# FE_Channel.net
KiCad netlist of a schematic drawn in Altium Designer
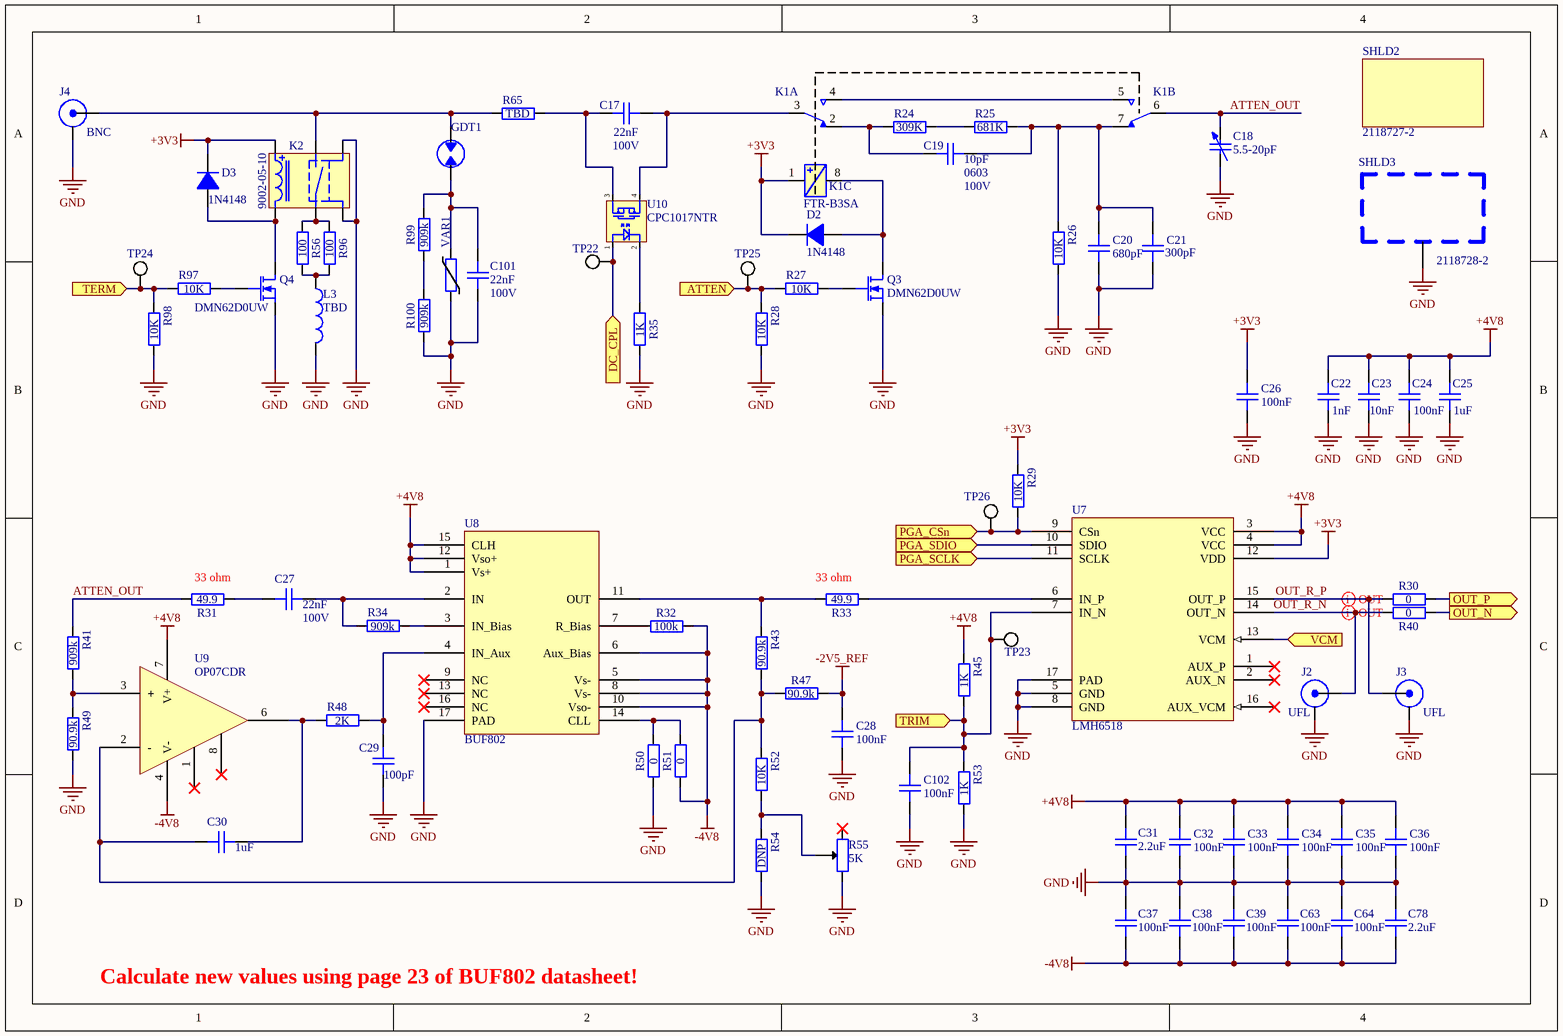
[diagram p0: FE_Channel.SchDoc]

(export (version "E")
  (design (tool "Eeschema 10.0.6"))
  (components
    (comp (ref "C17")
      (value "22nF")
      (footprint "GEN_C_0603")
      (fields (field (name "VOLTAGE RATING") "100V"))
      (libsource (lib "DSO") (part "CAP 22nF 100V X7R 0603"))
    )
    (comp (ref "C18")
      (value "5.5-20pF")
      (footprint "EW_TRIMCAP")
      (libsource (lib "DSO") (part "CAP TRIMMER 5.5-20PF 500V"))
    )
    (comp (ref "C19")
      (value "10pF")
      (footprint "GEN_C_0603")
      (fields (field (name "PACKAGE") "0603") (field (name "VOLTAGE RATING") "100V"))
      (libsource (lib "DSO") (part "CAP 10pF 100V C0G 0603"))
    )
    (comp (ref "C20")
      (value "680pF")
      (footprint "GEN_C_0402")
      (libsource (lib "DSO") (part "CAP 680pF 50V C0G 0402"))
    )
    (comp (ref "C21")
      (value "300pF")
      (footprint "GEN_C_0402")
      (libsource (lib "DSO") (part "CAP 300pF 50V C0G 0402"))
    )
    (comp (ref "C22")
      (value "1nF")
      (footprint "GEN_C_0402")
      (libsource (lib "DSO") (part "CAP 1nF 50V C0G 0402"))
    )
    (comp (ref "C23")
      (value "10nF")
      (footprint "GEN_C_0402")
      (libsource (lib "DSO") (part "CAP 10nF 50V X7R 0402"))
    )
    (comp (ref "C24")
      (value "100nF")
      (footprint "GEN_C_0402")
      (libsource (lib "DSO") (part "CAP 100nF 16V X7R 0402"))
    )
    (comp (ref "C25")
      (value "1uF")
      (footprint "GEN_C_0402")
      (libsource (lib "DSO") (part "CAP 1uF 25V X5R 0402"))
    )
    (comp (ref "C26")
      (value "100nF")
      (footprint "GEN_C_0402")
      (libsource (lib "DSO") (part "CAP 100nF 16V X7R 0402"))
    )
    (comp (ref "C27")
      (value "22nF")
      (footprint "GEN_C_0603")
      (fields (field (name "VOLTAGE RATING") "100V"))
      (libsource (lib "DSO") (part "CAP 22nF 100V X7R 0603"))
    )
    (comp (ref "C28")
      (value "100nF")
      (footprint "GEN_C_0402")
      (libsource (lib "DSO") (part "CAP 100nF 16V X7R 0402"))
    )
    (comp (ref "C29")
      (value "100pF")
      (footprint "GEN_C_0402")
      (libsource (lib "DSO") (part "CAP 100pF 50V C0G 0402"))
    )
    (comp (ref "C30")
      (value "1uF")
      (footprint "GEN_C_0402")
      (libsource (lib "DSO") (part "CAP 1uF 25V X5R 0402"))
    )
    (comp (ref "C31")
      (value "2.2uF")
      (footprint "GEN_C_0402")
      (libsource (lib "DSO") (part "CAP 2.2uF 10V X5R 0402"))
    )
    (comp (ref "C32")
      (value "100nF")
      (footprint "GEN_C_0402")
      (libsource (lib "DSO") (part "CAP 100nF 16V X7R 0402"))
    )
    (comp (ref "C33")
      (value "100nF")
      (footprint "GEN_C_0402")
      (libsource (lib "DSO") (part "CAP 100nF 16V X7R 0402"))
    )
    (comp (ref "C34")
      (value "100nF")
      (footprint "GEN_C_0402")
      (libsource (lib "DSO") (part "CAP 100nF 16V X7R 0402"))
    )
    (comp (ref "C35")
      (value "100nF")
      (footprint "GEN_C_0402")
      (libsource (lib "DSO") (part "CAP 100nF 16V X7R 0402"))
    )
    (comp (ref "C36")
      (value "100nF")
      (footprint "GEN_C_0402")
      (libsource (lib "DSO") (part "CAP 100nF 16V X7R 0402"))
    )
    (comp (ref "C37")
      (value "100nF")
      (footprint "GEN_C_0402")
      (libsource (lib "DSO") (part "CAP 100nF 16V X7R 0402"))
    )
    (comp (ref "C38")
      (value "100nF")
      (footprint "GEN_C_0402")
      (libsource (lib "DSO") (part "CAP 100nF 16V X7R 0402"))
    )
    (comp (ref "C39")
      (value "100nF")
      (footprint "GEN_C_0402")
      (libsource (lib "DSO") (part "CAP 100nF 16V X7R 0402"))
    )
    (comp (ref "C63")
      (value "100nF")
      (footprint "GEN_C_0402")
      (libsource (lib "DSO") (part "CAP 100nF 16V X7R 0402"))
    )
    (comp (ref "C64")
      (value "100nF")
      (footprint "GEN_C_0402")
      (libsource (lib "DSO") (part "CAP 100nF 16V X7R 0402"))
    )
    (comp (ref "C78")
      (value "2.2uF")
      (footprint "GEN_C_0402")
      (libsource (lib "DSO") (part "CAP 2.2uF 10V X5R 0402"))
    )
    (comp (ref "C101")
      (value "22nF")
      (footprint "GEN_C_0603")
      (fields (field (name "VOLTAGE RATING") "100V"))
      (libsource (lib "DSO") (part "CAP 22nF 100V X7R 0603"))
    )
    (comp (ref "C102")
      (value "100nF")
      (footprint "GEN_C_0402")
      (libsource (lib "DSO") (part "CAP 100nF 16V X7R 0402"))
    )
    (comp (ref "D2") (value "1N4148") (footprint "GEN_SOD_323") (libsource (lib "DSO") (part "DIODE 1N4148")))
    (comp (ref "D3") (value "1N4148") (footprint "GEN_SOD_323") (libsource (lib "DSO") (part "DIODE 1N4148")))
    (comp (ref "GDT1")
      (value "4532-075-LF")
      (footprint "BOU_2051")
      (libsource (lib "DSO") (part "GDT 75V 1812"))
    )
    (comp (ref "J2") (value "UFL") (footprint "TE_2334884-1") (libsource (lib "DSO") (part "UFL Jack SMD")))
    (comp (ref "J3") (value "UFL") (footprint "TE_2334884-1") (libsource (lib "DSO") (part "UFL Jack SMD")))
    (comp (ref "J4") (value "BNC") (footprint "MOL_0731000105") (libsource (lib "DSO") (part "BNC JACK R/A")))
    (comp (ref "K1")
      (value "FTR-B3SA")
      (footprint "FUJ_FTR-B3SA")
      (libsource (lib "DSO") (part "RELAY DPDT-NO FTR-B3SA"))
    )
    (comp (ref "K2")
      (value "9002-05-10")
      (footprint "COTO_9002-05-10")
      (libsource (lib "DSO") (part "RELAY RF SPST-NO 9002-05-10"))
    )
    (comp (ref "L3") (value "TBD") (footprint "GEN_L_0402") (libsource (lib "DSO") (part "IND TBD 0402")))
    (comp (ref "Q3")
      (value "DMN62D0UW")
      (footprint "GEN_SOT_323")
      (libsource (lib "DSO") (part "NMOS DMN62D0UW"))
    )
    (comp (ref "Q4")
      (value "DMN62D0UW")
      (footprint "GEN_SOT_323")
      (libsource (lib "DSO") (part "NMOS DMN62D0UW"))
    )
    (comp (ref "R24")
      (value "309K")
      (footprint "GEN_R_0402")
      (fields (field (name "TOLERANCE") "1%"))
      (libsource (lib "DSO") (part "RES 309K OHM 1% 1/16W 0402"))
    )
    (comp (ref "R25")
      (value "681K")
      (footprint "GEN_R_0402")
      (fields (field (name "TOLERANCE") "1%"))
      (libsource (lib "DSO") (part "RES 681K OHM 1% 1/16W 0402"))
    )
    (comp (ref "R26")
      (value "10K")
      (footprint "GEN_R_0402")
      (fields (field (name "TOLERANCE") "1%"))
      (libsource (lib "DSO") (part "RES 10K OHM 1% 1/10W 0402"))
    )
    (comp (ref "R27")
      (value "10K")
      (footprint "GEN_R_0402")
      (fields (field (name "TOLERANCE") "1%"))
      (libsource (lib "") (part "RES 10K OHM 1% 1/10W 0402_1"))
    )
    (comp (ref "R28")
      (value "10K")
      (footprint "GEN_R_0402")
      (fields (field (name "TOLERANCE") "1%"))
      (libsource (lib "DSO") (part "RES 10K OHM 1% 1/10W 0402"))
    )
    (comp (ref "R29")
      (value "10K")
      (footprint "GEN_R_0402")
      (fields (field (name "TOLERANCE") "1%"))
      (libsource (lib "DSO") (part "RES 10K OHM 1% 1/10W 0402"))
    )
    (comp (ref "R30")
      (value "0")
      (footprint "GEN_R_0402")
      (libsource (lib "") (part "RES 0 OHM 1/16W 0402_1"))
    )
    (comp (ref "R31")
      (value "49.9")
      (footprint "GEN_R_0402")
      (fields (field (name "TOLERANCE") "1%"))
      (libsource (lib "DSO") (part "RES 49.9 OHM 1% 1/10W 0402"))
    )
    (comp (ref "R32")
      (value "100k")
      (footprint "GEN_R_0402")
      (fields (field (name "TOLERANCE") "1%"))
      (libsource (lib "DSO") (part "RES 100K OHM 1% 1/10W 0402"))
    )
    (comp (ref "R33")
      (value "49.9")
      (footprint "GEN_R_0402")
      (fields (field (name "TOLERANCE") "1%"))
      (libsource (lib "DSO") (part "RES 49.9 OHM 1% 1/10W 0402"))
    )
    (comp (ref "R34")
      (value "909k")
      (footprint "GEN_R_0402")
      (fields (field (name "TOLERANCE") "1%"))
      (libsource (lib "DSO") (part "RES 909K OHM 1% 1/16W 0402"))
    )
    (comp (ref "R35")
      (value "1K")
      (footprint "GEN_R_0402")
      (fields (field (name "TOLERANCE") "1%"))
      (libsource (lib "") (part "RES 1K OHM 1% 1/10W 0402_1"))
    )
    (comp (ref "R40")
      (value "0")
      (footprint "GEN_R_0402")
      (libsource (lib "") (part "RES 0 OHM 1/16W 0402_1"))
    )
    (comp (ref "R41")
      (value "909k")
      (footprint "GEN_R_0402")
      (fields (field (name "TOLERANCE") "1%"))
      (libsource (lib "") (part "RES 909K OHM 1% 1/16W 0402_1"))
    )
    (comp (ref "R43")
      (value "90.9k")
      (footprint "GEN_R_0402")
      (fields (field (name "TOLERANCE") "1%"))
      (libsource (lib "DSO") (part "RES 90.9K OHM 1% 1/16W 0402"))
    )
    (comp (ref "R45")
      (value "1K")
      (footprint "GEN_R_0402")
      (fields (field (name "TOLERANCE") "1%"))
      (libsource (lib "DSO") (part "RES 1K OHM 1% 1/10W 0402"))
    )
    (comp (ref "R47")
      (value "90.9k")
      (footprint "GEN_R_0402")
      (fields (field (name "TOLERANCE") "1%"))
      (libsource (lib "") (part "RES 90.9K OHM 1% 1/16W 0402_1"))
    )
    (comp (ref "R48")
      (value "2K")
      (footprint "GEN_R_0402")
      (fields (field (name "TOLERANCE") "1%"))
      (libsource (lib "DSO") (part "RES 2K OHM 1% 1/16W 0402"))
    )
    (comp (ref "R49")
      (value "90.9k")
      (footprint "GEN_R_0402")
      (fields (field (name "TOLERANCE") "1%"))
      (libsource (lib "DSO") (part "RES 90.9K OHM 1% 1/16W 0402"))
    )
    (comp (ref "R50")
      (value "0")
      (footprint "GEN_R_0402")
      (libsource (lib "DSO") (part "RES 0 OHM 1/16W 0402"))
    )
    (comp (ref "R51")
      (value "0")
      (footprint "GEN_R_0402")
      (libsource (lib "DSO") (part "RES 0 OHM 1/16W 0402"))
    )
    (comp (ref "R52")
      (value "10K")
      (footprint "GEN_R_0402")
      (fields (field (name "TOLERANCE") "1%"))
      (libsource (lib "DSO") (part "RES 10K OHM 1% 1/10W 0402"))
    )
    (comp (ref "R53")
      (value "1K")
      (footprint "GEN_R_0402")
      (fields (field (name "TOLERANCE") "1%"))
      (libsource (lib "DSO") (part "RES 1K OHM 1% 1/10W 0402"))
    )
    (comp (ref "R54")
      (value "DNP")
      (footprint "GEN_R_0402")
      (fields (field (name "TOLERANCE") "1%"))
      (libsource (lib "DSO") (part "RES DNP 0402"))
    )
    (comp (ref "R55")
      (value "5K")
      (footprint "BOU_3mm_POT")
      (fields (field (name "TOLERANCE") "1%"))
      (libsource (lib "DSO") (part "TRIMMER 5K OHM 0.1W J LEAD TOP"))
    )
    (comp (ref "R56")
      (value "100")
      (footprint "GEN_R_0402")
      (fields (field (name "TOLERANCE") "1%"))
      (libsource (lib "DSO") (part "RES 100 OHM 1% 1/10W 0402"))
    )
    (comp (ref "R65") (value "TBD") (footprint "GEN_R_0603") (libsource (lib "DSO") (part "RES TBD 0603")))
    (comp (ref "R96")
      (value "100")
      (footprint "GEN_R_0402")
      (fields (field (name "TOLERANCE") "1%"))
      (libsource (lib "DSO") (part "RES 100 OHM 1% 1/10W 0402"))
    )
    (comp (ref "R97")
      (value "10K")
      (footprint "GEN_R_0402")
      (fields (field (name "TOLERANCE") "1%"))
      (libsource (lib "") (part "RES 10K OHM 1% 1/10W 0402_1"))
    )
    (comp (ref "R98")
      (value "10K")
      (footprint "GEN_R_0402")
      (fields (field (name "TOLERANCE") "1%"))
      (libsource (lib "DSO") (part "RES 10K OHM 1% 1/10W 0402"))
    )
    (comp (ref "R99")
      (value "909k")
      (footprint "GEN_R_0402")
      (fields (field (name "TOLERANCE") "1%"))
      (libsource (lib "") (part "RES 909K OHM 1% 1/16W 0402_1"))
    )
    (comp (ref "R100")
      (value "909k")
      (footprint "GEN_R_0402")
      (fields (field (name "TOLERANCE") "1%"))
      (libsource (lib "") (part "RES 909K OHM 1% 1/16W 0402_1"))
    )
    (comp (ref "SHLD2") (value "2118727-2") (libsource (lib "DSO") (part "SHIELD 2118727-2")))
    (comp (ref "SHLD3")
      (value "2118728-2")
      (footprint "TE_2118728-2")
      (libsource (lib "DSO") (part "SHIELD 2118728-2"))
    )
    (comp (ref "TP22") (value "PCB") (footprint "GEN_TP_PCB") (libsource (lib "DSO") (part "TP PCB 1mm")))
    (comp (ref "TP23") (value "PCB") (footprint "GEN_TP_PCB") (libsource (lib "DSO") (part "TP PCB 1mm")))
    (comp (ref "TP24") (value "PCB") (footprint "GEN_TP_PCB") (libsource (lib "DSO") (part "TP PCB 1mm")))
    (comp (ref "TP25") (value "PCB") (footprint "GEN_TP_PCB") (libsource (lib "DSO") (part "TP PCB 1mm")))
    (comp (ref "TP26") (value "PCB") (footprint "GEN_TP_PCB") (libsource (lib "DSO") (part "TP PCB 1mm")))
    (comp (ref "U7")
      (value "LMH6518")
      (footprint "TI_WQFN_RGH0016A")
      (libsource (lib "DSO") (part "IC PGA LMH6518"))
    )
    (comp (ref "U8")
      (value "BUF802")
      (footprint "TI_VQFN_RGT0016C")
      (libsource (lib "DSO") (part "IC BUFFER AMP BUF802"))
    )
    (comp (ref "U9")
      (value "OP07CDR")
      (footprint "TI_SOIC8_D0008A")
      (libsource (lib "DSO") (part "IC OPAMP OP07CDR"))
    )
    (comp (ref "U10")
      (value "CPC1017NTR")
      (footprint "IXY_CPC1017")
      (libsource (lib "DSO") (part "SSR CPC1017NTR"))
    )
    (comp (ref "VAR1")
      (value "ZV40K1210251NIR1HT")
      (footprint "GEN_VAR_1210")
      (libsource (lib "DSO") (part "VARISTOR 68V 250A 1210"))
    )
  )
  (nets
    (net (code "1") (name "+3V3") (class "Default")
      (node (ref "C26") (pin "2") (pinfunction "2_2") (pintype "passive"))
      (node (ref "D2") (pin "1") (pinfunction "K_1") (pintype "passive"))
      (node (ref "D3") (pin "1") (pinfunction "K_1") (pintype "passive"))
      (node (ref "K1") (pin "1") (pinfunction "1_1") (pintype "passive"))
      (node (ref "K2") (pin "2") (pinfunction "2_2") (pintype "passive"))
      (node (ref "R29") (pin "2") (pinfunction "2_2") (pintype "passive"))
      (node (ref "U7") (pin "12") (pinfunction "VDD_12") (pintype "power_in"))
    )
    (net (code "2") (name "+4V8") (class "Default")
      (node (ref "C22") (pin "2") (pinfunction "2_2") (pintype "passive"))
      (node (ref "C23") (pin "2") (pinfunction "2_2") (pintype "passive"))
      (node (ref "C24") (pin "2") (pinfunction "2_2") (pintype "passive"))
      (node (ref "C25") (pin "2") (pinfunction "2_2") (pintype "passive"))
      (node (ref "C31") (pin "2") (pinfunction "2_2") (pintype "passive"))
      (node (ref "C32") (pin "1") (pinfunction "1_1") (pintype "passive"))
      (node (ref "C33") (pin "1") (pinfunction "1_1") (pintype "passive"))
      (node (ref "C34") (pin "1") (pinfunction "1_1") (pintype "passive"))
      (node (ref "C35") (pin "2") (pinfunction "2_2") (pintype "passive"))
      (node (ref "C36") (pin "2") (pinfunction "2_2") (pintype "passive"))
      (node (ref "R45") (pin "2") (pinfunction "2_2") (pintype "passive"))
      (node (ref "U7") (pin "3") (pinfunction "VCC_3") (pintype "power_in"))
      (node (ref "U7") (pin "4") (pinfunction "VCC_4") (pintype "power_in"))
      (node (ref "U8") (pin "1") (pinfunction "Vs+_1") (pintype "passive"))
      (node (ref "U8") (pin "12") (pinfunction "Vso+_12") (pintype "passive"))
      (node (ref "U8") (pin "15") (pinfunction "CLH_15") (pintype "passive"))
      (node (ref "U9") (pin "7") (pinfunction "V+_7") (pintype "passive"))
    )
    (net (code "3") (name "-2V5_REF") (class "Default")
      (node (ref "C28") (pin "1") (pinfunction "1_1") (pintype "passive"))
      (node (ref "R47") (pin "1") (pinfunction "1_1") (pintype "passive"))
    )
    (net (code "4") (name "-4V8") (class "Default")
      (node (ref "C37") (pin "2") (pinfunction "2_2") (pintype "passive"))
      (node (ref "C38") (pin "2") (pinfunction "2_2") (pintype "passive"))
      (node (ref "C39") (pin "1") (pinfunction "1_1") (pintype "passive"))
      (node (ref "C63") (pin "1") (pinfunction "1_1") (pintype "passive"))
      (node (ref "C64") (pin "1") (pinfunction "1_1") (pintype "passive"))
      (node (ref "C78") (pin "2") (pinfunction "2_2") (pintype "passive"))
      (node (ref "R32") (pin "2") (pinfunction "2_2") (pintype "passive"))
      (node (ref "R51") (pin "1") (pinfunction "1_1") (pintype "passive"))
      (node (ref "U8") (pin "10") (pinfunction "Vso-_10") (pintype "passive"))
      (node (ref "U8") (pin "5") (pinfunction "Vs-_5") (pintype "passive"))
      (node (ref "U8") (pin "6") (pinfunction "Aux_Bias_6") (pintype "passive"))
      (node (ref "U8") (pin "8") (pinfunction "Vs-_8") (pintype "passive"))
      (node (ref "U9") (pin "4") (pinfunction "V-_4") (pintype "passive"))
    )
    (net (code "5") (name "/ATTEN") (class "Default")
      (node (ref "R27") (pin "2") (pinfunction "2_2") (pintype "passive"))
      (node (ref "R28") (pin "2") (pinfunction "2_2") (pintype "passive"))
      (node (ref "TP25") (pin "1") (pinfunction "1_1") (pintype "passive"))
    )
    (net (code "6") (name "/ATTEN_OUT") (class "Default")
      (node (ref "C18") (pin "1") (pinfunction "1_1") (pintype "passive"))
      (node (ref "K1") (pin "6") (pinfunction "6_6") (pintype "passive"))
      (node (ref "R31") (pin "1") (pinfunction "1_1") (pintype "passive"))
      (node (ref "R41") (pin "2") (pinfunction "2_2") (pintype "passive"))
    )
    (net (code "7") (name "/DC_CPL") (class "Default")
      (node (ref "TP22") (pin "1") (pinfunction "1_1") (pintype "passive"))
      (node (ref "U10") (pin "1") (pinfunction "1_1") (pintype "passive"))
    )
    (net (code "8") (name "/OUT_N") (class "Default")
      (node (ref "R40") (pin "2") (pinfunction "2_2") (pintype "passive"))
    )
    (net (code "9") (name "/OUT_P") (class "Default")
      (node (ref "R30") (pin "2") (pinfunction "2_2") (pintype "passive"))
    )
    (net (code "10") (name "/OUT_R_N") (class "Default")
      (node (ref "J2") (pin "1") (pinfunction "Signal_1") (pintype "passive"))
      (node (ref "R40") (pin "1") (pinfunction "1_1") (pintype "passive"))
      (node (ref "U7") (pin "14") (pinfunction "OUT_N_14") (pintype "passive"))
    )
    (net (code "11") (name "/OUT_R_P") (class "Default")
      (node (ref "J3") (pin "1") (pinfunction "Signal_1") (pintype "passive"))
      (node (ref "R30") (pin "1") (pinfunction "1_1") (pintype "passive"))
      (node (ref "U7") (pin "15") (pinfunction "OUT_P_15") (pintype "passive"))
    )
    (net (code "12") (name "/PGA_CSn") (class "Default")
      (node (ref "R29") (pin "1") (pinfunction "1_1") (pintype "passive"))
      (node (ref "TP26") (pin "1") (pinfunction "1_1") (pintype "passive"))
      (node (ref "U7") (pin "9") (pinfunction "CSn_9") (pintype "passive"))
    )
    (net (code "13") (name "/PGA_SCLK") (class "Default")
      (node (ref "U7") (pin "11") (pinfunction "SCLK_11") (pintype "passive"))
    )
    (net (code "14") (name "/PGA_SDIO") (class "Default")
      (node (ref "U7") (pin "10") (pinfunction "SDIO_10") (pintype "passive"))
    )
    (net (code "15") (name "/TERM") (class "Default")
      (node (ref "R97") (pin "2") (pinfunction "2_2") (pintype "passive"))
      (node (ref "R98") (pin "2") (pinfunction "2_2") (pintype "passive"))
      (node (ref "TP24") (pin "1") (pinfunction "1_1") (pintype "passive"))
    )
    (net (code "16") (name "/TRIM") (class "Default")
      (node (ref "C102") (pin "1") (pinfunction "1_1") (pintype "passive"))
      (node (ref "R45") (pin "1") (pinfunction "1_1") (pintype "passive"))
      (node (ref "R53") (pin "2") (pinfunction "2_2") (pintype "passive"))
      (node (ref "TP23") (pin "1") (pinfunction "1_1") (pintype "passive"))
      (node (ref "U7") (pin "7") (pinfunction "IN_N_7") (pintype "passive"))
    )
    (net (code "17") (name "/VCM") (class "Default")
      (node (ref "U7") (pin "13") (pinfunction "VCM_13") (pintype "input"))
    )
    (net (code "18") (name "GND") (class "Default")
      (node (ref "C101") (pin "2") (pinfunction "2_2") (pintype "passive"))
      (node (ref "C102") (pin "2") (pinfunction "2_2") (pintype "passive"))
      (node (ref "C18") (pin "2") (pinfunction "2_2") (pintype "passive"))
      (node (ref "C20") (pin "1") (pinfunction "1_1") (pintype "passive"))
      (node (ref "C21") (pin "1") (pinfunction "1_1") (pintype "passive"))
      (node (ref "C22") (pin "1") (pinfunction "1_1") (pintype "passive"))
      (node (ref "C23") (pin "1") (pinfunction "1_1") (pintype "passive"))
      (node (ref "C24") (pin "1") (pinfunction "1_1") (pintype "passive"))
      (node (ref "C25") (pin "1") (pinfunction "1_1") (pintype "passive"))
      (node (ref "C26") (pin "1") (pinfunction "1_1") (pintype "passive"))
      (node (ref "C28") (pin "2") (pinfunction "2_2") (pintype "passive"))
      (node (ref "C29") (pin "1") (pinfunction "1_1") (pintype "passive"))
      (node (ref "C31") (pin "1") (pinfunction "1_1") (pintype "passive"))
      (node (ref "C32") (pin "2") (pinfunction "2_2") (pintype "passive"))
      (node (ref "C33") (pin "2") (pinfunction "2_2") (pintype "passive"))
      (node (ref "C34") (pin "2") (pinfunction "2_2") (pintype "passive"))
      (node (ref "C35") (pin "1") (pinfunction "1_1") (pintype "passive"))
      (node (ref "C36") (pin "1") (pinfunction "1_1") (pintype "passive"))
      (node (ref "C37") (pin "1") (pinfunction "1_1") (pintype "passive"))
      (node (ref "C38") (pin "1") (pinfunction "1_1") (pintype "passive"))
      (node (ref "C39") (pin "2") (pinfunction "2_2") (pintype "passive"))
      (node (ref "C63") (pin "2") (pinfunction "2_2") (pintype "passive"))
      (node (ref "C64") (pin "2") (pinfunction "2_2") (pintype "passive"))
      (node (ref "C78") (pin "1") (pinfunction "1_1") (pintype "passive"))
      (node (ref "J2") (pin "2") (pinfunction "SHIELD_2") (pintype "passive"))
      (node (ref "J3") (pin "2") (pinfunction "SHIELD_2") (pintype "passive"))
      (node (ref "J4") (pin "2") (pinfunction "SHIELD_2") (pintype "passive"))
      (node (ref "K2") (pin "5") (pinfunction "5_5") (pintype "passive"))
      (node (ref "K2") (pin "6") (pinfunction "6_6") (pintype "passive"))
      (node (ref "L3") (pin "2") (pinfunction "2_2") (pintype "passive"))
      (node (ref "Q3") (pin "3") (pinfunction "S_3") (pintype "passive"))
      (node (ref "Q4") (pin "3") (pinfunction "S_3") (pintype "passive"))
      (node (ref "R100") (pin "1") (pinfunction "1_1") (pintype "passive"))
      (node (ref "R26") (pin "1") (pinfunction "1_1") (pintype "passive"))
      (node (ref "R28") (pin "1") (pinfunction "1_1") (pintype "passive"))
      (node (ref "R35") (pin "1") (pinfunction "1_1") (pintype "passive"))
      (node (ref "R49") (pin "1") (pinfunction "1_1") (pintype "passive"))
      (node (ref "R50") (pin "1") (pinfunction "1_1") (pintype "passive"))
      (node (ref "R53") (pin "1") (pinfunction "1_1") (pintype "passive"))
      (node (ref "R54") (pin "1") (pinfunction "1_1") (pintype "passive"))
      (node (ref "R55") (pin "3") (pinfunction "3_3") (pintype "passive"))
      (node (ref "R98") (pin "1") (pinfunction "1_1") (pintype "passive"))
      (node (ref "SHLD3") (pin "1") (pinfunction "1_1") (pintype "passive"))
      (node (ref "U7") (pin "17") (pinfunction "PAD_17") (pintype "power_in"))
      (node (ref "U7") (pin "5") (pinfunction "GND_5") (pintype "power_in"))
      (node (ref "U7") (pin "8") (pinfunction "GND_8") (pintype "power_in"))
      (node (ref "U8") (pin "17") (pinfunction "PAD_17") (pintype "passive"))
      (node (ref "VAR1") (pin "1") (pinfunction "1_1") (pintype "passive"))
    )
    (net (code "19") (name "Net-(C17-Pad1)") (class "Default")
      (node (ref "C17") (pin "1") (pinfunction "1_1") (pintype "passive"))
      (node (ref "K1") (pin "3") (pinfunction "3_3") (pintype "passive"))
      (node (ref "U10") (pin "4") (pinfunction "4_4") (pintype "passive"))
    )
    (net (code "20") (name "Net-(C17-Pad2)") (class "Default")
      (node (ref "C17") (pin "2") (pinfunction "2_2") (pintype "passive"))
      (node (ref "R65") (pin "2") (pinfunction "2_2") (pintype "passive"))
      (node (ref "U10") (pin "3") (pinfunction "3_3") (pintype "passive"))
    )
    (net (code "21") (name "Net-(C19-Pad1)") (class "Default")
      (node (ref "C19") (pin "1") (pinfunction "1_1") (pintype "passive"))
      (node (ref "C20") (pin "2") (pinfunction "2_2") (pintype "passive"))
      (node (ref "C21") (pin "2") (pinfunction "2_2") (pintype "passive"))
      (node (ref "K1") (pin "7") (pinfunction "7_7") (pintype "passive"))
      (node (ref "R25") (pin "2") (pinfunction "2_2") (pintype "passive"))
      (node (ref "R26") (pin "2") (pinfunction "2_2") (pintype "passive"))
    )
    (net (code "22") (name "Net-(C19-Pad2)") (class "Default")
      (node (ref "C19") (pin "2") (pinfunction "2_2") (pintype "passive"))
      (node (ref "K1") (pin "2") (pinfunction "2_2") (pintype "passive"))
      (node (ref "R24") (pin "1") (pinfunction "1_1") (pintype "passive"))
    )
    (net (code "23") (name "Net-(C27-Pad2)") (class "Default")
      (node (ref "C27") (pin "2") (pinfunction "2_2") (pintype "passive"))
      (node (ref "R31") (pin "2") (pinfunction "2_2") (pintype "passive"))
    )
    (net (code "24") (name "Net-(C101-Pad1)") (class "Default")
      (node (ref "C101") (pin "1") (pinfunction "1_1") (pintype "passive"))
      (node (ref "GDT1") (pin "2") (pinfunction "2_2") (pintype "passive"))
      (node (ref "R99") (pin "2") (pinfunction "2_2") (pintype "passive"))
      (node (ref "VAR1") (pin "2") (pinfunction "2_2") (pintype "passive"))
    )
    (net (code "25") (name "Net-(D2-A)") (class "Default")
      (node (ref "D2") (pin "2") (pinfunction "A_2") (pintype "passive"))
      (node (ref "K1") (pin "8") (pinfunction "8_8") (pintype "passive"))
      (node (ref "Q3") (pin "1") (pinfunction "D_1") (pintype "passive"))
    )
    (net (code "26") (name "Net-(D3-A)") (class "Default")
      (node (ref "D3") (pin "2") (pinfunction "A_2") (pintype "passive"))
      (node (ref "K2") (pin "3") (pinfunction "3_3") (pintype "passive"))
      (node (ref "Q4") (pin "1") (pinfunction "D_1") (pintype "passive"))
    )
    (net (code "27") (name "Net-(J4-Signal)") (class "Default")
      (node (ref "GDT1") (pin "1") (pinfunction "1_1") (pintype "passive"))
      (node (ref "J4") (pin "1") (pinfunction "Signal_1") (pintype "passive"))
      (node (ref "K2") (pin "1") (pinfunction "1_1") (pintype "passive"))
      (node (ref "R65") (pin "1") (pinfunction "1_1") (pintype "passive"))
    )
    (net (code "28") (name "Net-(K1-Pad4)") (class "Default")
      (node (ref "K1") (pin "4") (pinfunction "4_4") (pintype "passive"))
      (node (ref "K1") (pin "5") (pinfunction "5_5") (pintype "passive"))
    )
    (net (code "29") (name "Net-(K2-Pad4)") (class "Default")
      (node (ref "K2") (pin "4") (pinfunction "4_4") (pintype "passive"))
      (node (ref "R56") (pin "2") (pinfunction "2_2") (pintype "passive"))
      (node (ref "R96") (pin "2") (pinfunction "2_2") (pintype "passive"))
    )
    (net (code "30") (name "Net-(L3-Pad1)") (class "Default")
      (node (ref "L3") (pin "1") (pinfunction "1_1") (pintype "passive"))
      (node (ref "R56") (pin "1") (pinfunction "1_1") (pintype "passive"))
      (node (ref "R96") (pin "1") (pinfunction "1_1") (pintype "passive"))
    )
    (net (code "31") (name "Net-(Q3-G)") (class "Default")
      (node (ref "Q3") (pin "2") (pinfunction "G_2") (pintype "passive"))
      (node (ref "R27") (pin "1") (pinfunction "1_1") (pintype "passive"))
    )
    (net (code "32") (name "Net-(Q4-G)") (class "Default")
      (node (ref "Q4") (pin "2") (pinfunction "G_2") (pintype "passive"))
      (node (ref "R97") (pin "1") (pinfunction "1_1") (pintype "passive"))
    )
    (net (code "33") (name "Net-(R24-Pad2)") (class "Default")
      (node (ref "R24") (pin "2") (pinfunction "2_2") (pintype "passive"))
      (node (ref "R25") (pin "1") (pinfunction "1_1") (pintype "passive"))
    )
    (net (code "34") (name "Net-(R35-Pad2)") (class "Default")
      (node (ref "R35") (pin "2") (pinfunction "2_2") (pintype "passive"))
      (node (ref "U10") (pin "2") (pinfunction "2_2") (pintype "passive"))
    )
    (net (code "35") (name "Net-(R52-Pad1)") (class "Default")
      (node (ref "R52") (pin "1") (pinfunction "1_1") (pintype "passive"))
      (node (ref "R54") (pin "2") (pinfunction "2_2") (pintype "passive"))
      (node (ref "R55") (pin "2") (pinfunction "2_2") (pintype "passive"))
    )
    (net (code "36") (name "Net-(R100-Pad2)") (class "Default")
      (node (ref "R100") (pin "2") (pinfunction "2_2") (pintype "passive"))
      (node (ref "R99") (pin "1") (pinfunction "1_1") (pintype "passive"))
    )
    (net (code "37") (name "Net-(U7-IN_P)") (class "Default")
      (node (ref "R33") (pin "2") (pinfunction "2_2") (pintype "passive"))
      (node (ref "U7") (pin "6") (pinfunction "IN_P_6") (pintype "passive"))
    )
    (net (code "38") (name "Net-(U8-CLL)") (class "Default")
      (node (ref "R50") (pin "2") (pinfunction "2_2") (pintype "passive"))
      (node (ref "R51") (pin "2") (pinfunction "2_2") (pintype "passive"))
      (node (ref "U8") (pin "14") (pinfunction "CLL_14") (pintype "passive"))
    )
    (net (code "39") (name "Net-(U8-IN)") (class "Default")
      (node (ref "C27") (pin "1") (pinfunction "1_1") (pintype "passive"))
      (node (ref "R34") (pin "2") (pinfunction "2_2") (pintype "passive"))
      (node (ref "U8") (pin "2") (pinfunction "IN_2") (pintype "passive"))
    )
    (net (code "40") (name "Net-(U8-IN_Aux)") (class "Default")
      (node (ref "C29") (pin "2") (pinfunction "2_2") (pintype "passive"))
      (node (ref "R48") (pin "1") (pinfunction "1_1") (pintype "passive"))
      (node (ref "U8") (pin "4") (pinfunction "IN_Aux_4") (pintype "passive"))
    )
    (net (code "41") (name "Net-(U8-IN_Bias)") (class "Default")
      (node (ref "R34") (pin "1") (pinfunction "1_1") (pintype "passive"))
      (node (ref "U8") (pin "3") (pinfunction "IN_Bias_3") (pintype "passive"))
    )
    (net (code "42") (name "Net-(U8-OUT)") (class "Default")
      (node (ref "R33") (pin "1") (pinfunction "1_1") (pintype "passive"))
      (node (ref "R43") (pin "2") (pinfunction "2_2") (pintype "passive"))
      (node (ref "U8") (pin "11") (pinfunction "OUT_11") (pintype "passive"))
    )
    (net (code "43") (name "Net-(U8-R_Bias)") (class "Default")
      (node (ref "R32") (pin "1") (pinfunction "1_1") (pintype "passive"))
      (node (ref "U8") (pin "7") (pinfunction "R_Bias_7") (pintype "passive"))
    )
    (net (code "44") (name "Net-(U9-+)") (class "Default")
      (node (ref "R41") (pin "1") (pinfunction "1_1") (pintype "passive"))
      (node (ref "R49") (pin "2") (pinfunction "2_2") (pintype "passive"))
      (node (ref "U9") (pin "3") (pinfunction "+_3") (pintype "passive"))
    )
    (net (code "45") (name "Net-(U9--)") (class "Default")
      (node (ref "C30") (pin "2") (pinfunction "2_2") (pintype "passive"))
      (node (ref "R43") (pin "1") (pinfunction "1_1") (pintype "passive"))
      (node (ref "R47") (pin "2") (pinfunction "2_2") (pintype "passive"))
      (node (ref "R52") (pin "2") (pinfunction "2_2") (pintype "passive"))
      (node (ref "U9") (pin "2") (pinfunction "-_2") (pintype "passive"))
    )
    (net (code "46") (name "Net-(U9-OUT)") (class "Default")
      (node (ref "C30") (pin "1") (pinfunction "1_1") (pintype "passive"))
      (node (ref "R48") (pin "2") (pinfunction "2_2") (pintype "passive"))
      (node (ref "U9") (pin "6") (pinfunction "OUT_6") (pintype "passive"))
    )
    (net (code "47") (name "unconnected-(R55-Pad1)") (class "Default")
      (node (ref "R55") (pin "1") (pinfunction "1_1") (pintype "passive+no_connect"))
    )
    (net (code "48") (name "unconnected-(U7-AUX_N-Pad2)") (class "Default")
      (node (ref "U7") (pin "2") (pinfunction "AUX_N_2") (pintype "passive+no_connect"))
    )
    (net (code "49") (name "unconnected-(U7-AUX_P-Pad1)") (class "Default")
      (node (ref "U7") (pin "1") (pinfunction "AUX_P_1") (pintype "passive+no_connect"))
    )
    (net (code "50") (name "unconnected-(U7-AUX_VCM-Pad16)") (class "Default")
      (node (ref "U7") (pin "16") (pinfunction "AUX_VCM_16") (pintype "input+no_connect"))
    )
    (net (code "51") (name "unconnected-(U8-NC-Pad9)") (class "Default")
      (node (ref "U8") (pin "9") (pinfunction "NC_9") (pintype "passive+no_connect"))
    )
    (net (code "52") (name "unconnected-(U8-NC-Pad13)") (class "Default")
      (node (ref "U8") (pin "13") (pinfunction "NC_13") (pintype "passive+no_connect"))
    )
    (net (code "53") (name "unconnected-(U8-NC-Pad16)") (class "Default")
      (node (ref "U8") (pin "16") (pinfunction "NC_16") (pintype "passive+no_connect"))
    )
    (net (code "54") (name "unconnected-(U9-N1-Pad1)") (class "Default")
      (node (ref "U9") (pin "1") (pinfunction "N1_1") (pintype "passive+no_connect"))
    )
    (net (code "55") (name "unconnected-(U9-N2-Pad8)") (class "Default")
      (node (ref "U9") (pin "8") (pinfunction "N2_8") (pintype "passive+no_connect"))
    )
  )
)
